# Power_Stage.net
KiCad netlist of a schematic drawn in Altium Designer
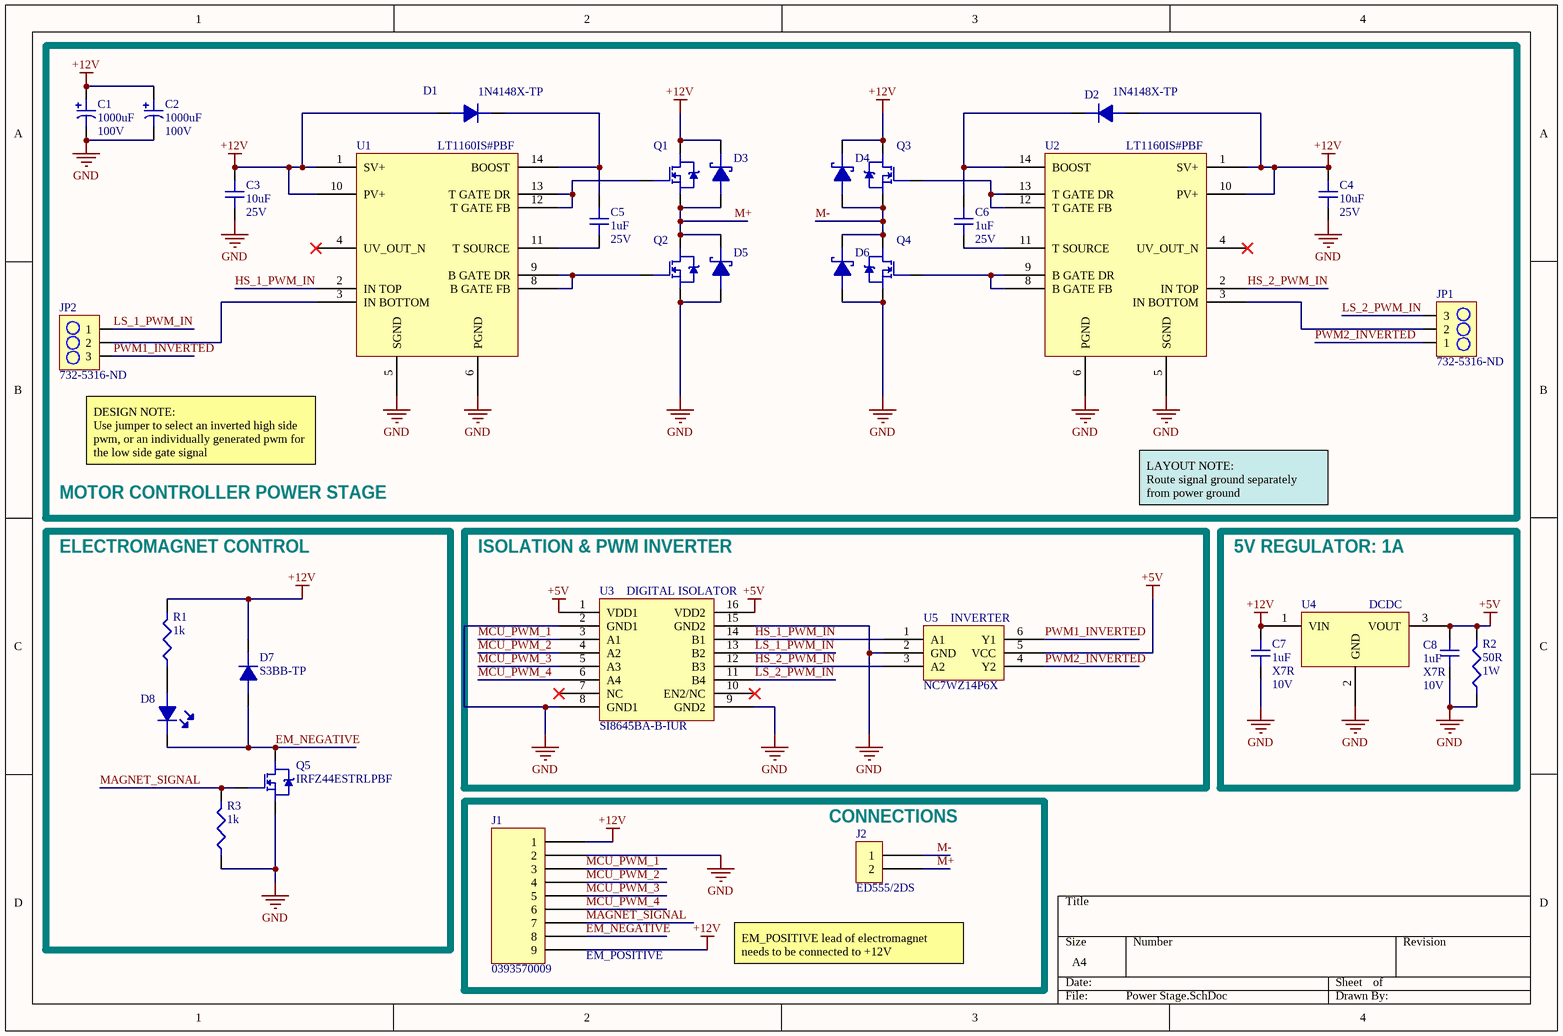
[diagram p0: Power Stage.SchDoc]

(export (version "E")
  (design (tool "Eeschema 10.0.6"))
  (components
    (comp (ref "C1")
      (value "UVR2A102MRD6")
      (footprint "CAP_THRU")
      (description "CAP Electrolytic 1000uF 100V")
      (fields
        (field (name "MANUFACTURER") "Nichicon")
        (field (name "TOLERANCE") "20%")
        (field (name "CAPACITANCE") "1000uF")
        (field (name "VOLTAGE RATING") "100V")
      )
      (libsource (lib "SCH_SYMBOLS") (part "UVR2A102MRD6"))
    )
    (comp (ref "C2")
      (value "UVR2A102MRD6")
      (footprint "CAP_THRU")
      (description "CAP Electrolytic 1000uF 100V")
      (fields
        (field (name "MANUFACTURER") "Nichicon")
        (field (name "TOLERANCE") "20%")
        (field (name "CAPACITANCE") "1000uF")
        (field (name "VOLTAGE RATING") "100V")
      )
      (libsource (lib "SCH_SYMBOLS") (part "UVR2A102MRD6"))
    )
    (comp (ref "C3")
      (value "C3216X5R1E106K160AB")
      (footprint "C1206")
      (fields
        (field (name "MANUFACTURER") "TDK")
        (field (name "TOLERANCE") "10%")
        (field (name "CAPACITANCE") "10uF")
        (field (name "VOLTAGE RATING") "25V")
      )
      (libsource (lib "SCH_SYMBOLS") (part "C3216X5R1E106K160AB"))
    )
    (comp (ref "C4")
      (value "C3216X5R1E106K160AB")
      (footprint "C1206")
      (fields
        (field (name "MANUFACTURER") "TDK")
        (field (name "TOLERANCE") "10%")
        (field (name "CAPACITANCE") "10uF")
        (field (name "VOLTAGE RATING") "25V")
      )
      (libsource (lib "SCH_SYMBOLS") (part "C3216X5R1E106K160AB"))
    )
    (comp (ref "C5")
      (value "1uF")
      (footprint "C0805")
      (description "CAP MLCC 1UF 25V X7R 0805")
      (fields
        (field (name "MANUFACTURER") "Murata")
        (field (name "MANUFACTURER PART NUMBER") "GCM21BR71E105KA56L")
        (field (name "CAPACITANCE") "1uF")
        (field (name "VOLTAGE") "25V")
      )
      (libsource (lib "SCH_SYMBOLS") (part "GCM21BR71E105KA56L"))
    )
    (comp (ref "C6")
      (value "1uF")
      (footprint "C0805")
      (description "CAP MLCC 1UF 25V X7R 0805")
      (fields
        (field (name "MANUFACTURER") "Murata")
        (field (name "MANUFACTURER PART NUMBER") "GCM21BR71E105KA56L")
        (field (name "CAPACITANCE") "1uF")
        (field (name "VOLTAGE") "25V")
      )
      (libsource (lib "SCH_SYMBOLS") (part "GCM21BR71E105KA56L"))
    )
    (comp (ref "C7")
      (value "1uF")
      (footprint "C0805")
      (description "CAP CER 1UF 10V X7R 0805")
      (fields
        (field (name "MANUFACTURER") "Kyocera AVX")
        (field (name "MANUFACTURER PART NUMBER") "0805ZC105KAT2A")
        (field (name "DIELECTRIC") "X7R")
        (field (name "VOLTAGE") "10V")
      )
      (libsource (lib "SCH_SYMBOLS") (part "0805ZC105KAT2A"))
    )
    (comp (ref "C8")
      (value "1uF")
      (footprint "C0805")
      (description "CAP CER 1UF 10V X7R 0805")
      (fields
        (field (name "MANUFACTURER") "Kyocera AVX")
        (field (name "MANUFACTURER PART NUMBER") "0805ZC105KAT2A")
        (field (name "DIELECTRIC") "X7R")
        (field (name "VOLTAGE") "10V")
      )
      (libsource (lib "SCH_SYMBOLS") (part "0805ZC105KAT2A"))
    )
    (comp (ref "D1")
      (value "1N4148X-TP")
      (footprint "SOD523")
      (description "DIODE GEN PURP 75V 150MA SOD523")
      (fields (field (name "MANUFACTURER") "MCC"))
      (libsource (lib "SCH_SYMBOLS") (part "1N4148X-TP"))
    )
    (comp (ref "D2")
      (value "1N4148X-TP")
      (footprint "SOD523")
      (description "DIODE GEN PURP 75V 150MA SOD523")
      (fields (field (name "MANUFACTURER") "MCC"))
      (libsource (lib "SCH_SYMBOLS") (part "1N4148X-TP"))
    )
    (comp (ref "D3")
      (value "CDBA540-HF")
      (footprint "DO214-AC")
      (description "DIODE Schottky Diodes & Rectifiers 40V, 5A")
      (fields (field (name "MANUFACTURER") "Comchip"))
      (libsource (lib "SCH_SYMBOLS") (part "CDBA540-HF"))
    )
    (comp (ref "D4")
      (value "CDBA540-HF")
      (footprint "DO214-AC")
      (description "DIODE Schottky Diodes & Rectifiers 40V, 5A")
      (fields (field (name "MANUFACTURER") "Comchip"))
      (libsource (lib "SCH_SYMBOLS") (part "CDBA540-HF"))
    )
    (comp (ref "D5")
      (value "CDBA540-HF")
      (footprint "DO214-AC")
      (description "DIODE Schottky Diodes & Rectifiers 40V, 5A")
      (fields (field (name "MANUFACTURER") "Comchip"))
      (libsource (lib "SCH_SYMBOLS") (part "CDBA540-HF"))
    )
    (comp (ref "D6")
      (value "CDBA540-HF")
      (footprint "DO214-AC")
      (description "DIODE Schottky Diodes & Rectifiers 40V, 5A")
      (fields (field (name "MANUFACTURER") "Comchip"))
      (libsource (lib "SCH_SYMBOLS") (part "CDBA540-HF"))
    )
    (comp (ref "D7")
      (value "S3BB-TP")
      (footprint "DO-214AA_Diode")
      (description "DIODE GEN PURP 100V 3A DO214AA")
      (fields (field (name "MANUFACTURER") "MCC"))
      (libsource (lib "SCH_SYMBOLS") (part "S3BB-TP"))
    )
    (comp (ref "D8")
      (value "LTST-C191TBKT-5A")
      (footprint "LED_0603")
      (description "LED BLUE CLEAR 0603 SMD")
      (fields (field (name "MANUFACTURER") "Vishay Lite-On") (field (name "VOLTAGE") "29V"))
      (libsource (lib "SCH_SYMBOLS") (part "LTST-C191TBKT-5A"))
    )
    (comp (ref "J1")
      (value "0393570009")
      (footprint "9POS_CONNECTOR")
      (description "CONN TERMINAL BLOCK 9POS 3.5MM")
      (fields (field (name "MANUFACTURER") "Molex") (field (name "VOLTAGE") "300V"))
      (libsource (lib "SCH_SYMBOLS") (part "0393570009"))
    )
    (comp (ref "J2")
      (value "ED555/2DS")
      (footprint "2POS_CONNECTOR")
      (description "TERMINAL BLOCK 3.5MM 2POS PCB")
      (fields (field (name "MANUFACTURER") "On-Shore Technology") (field (name "VOLTAGE") "150V"))
      (libsource (lib "SCH_SYMBOLS") (part "ED555/2DS"))
    )
    (comp (ref "JP1")
      (value "732-5316-ND")
      (footprint "3PIN_HEADER")
      (fields
        (field (name "MANUFACTURER") "Wurth Electronics")
        (field (name "MANUFACTURER PART NUMBER") "61300311121")
      )
      (libsource (lib "SCH_SYMBOLS") (part "61300311121"))
    )
    (comp (ref "JP2")
      (value "732-5316-ND")
      (footprint "3PIN_HEADER")
      (fields
        (field (name "MANUFACTURER") "Wurth Electronics")
        (field (name "MANUFACTURER PART NUMBER") "61300311121")
      )
      (libsource (lib "") (part "61300311121_1"))
    )
    (comp (ref "Q1")
      (value "IRFZ44ESTRLPBF")
      (footprint "D2PAK")
      (description "MOSFET N-CH 60V 48A D2PAK")
      (fields (field (name "MANUFACTURER") "Infineon"))
      (libsource (lib "SCH_SYMBOLS") (part "IRFZ44ESTRLPBF"))
    )
    (comp (ref "Q2")
      (value "IRFZ44ESTRLPBF")
      (footprint "D2PAK")
      (description "MOSFET N-CH 60V 48A D2PAK")
      (fields (field (name "MANUFACTURER") "Infineon"))
      (libsource (lib "SCH_SYMBOLS") (part "IRFZ44ESTRLPBF"))
    )
    (comp (ref "Q3")
      (value "IRFZ44ESTRLPBF")
      (footprint "D2PAK")
      (description "MOSFET N-CH 60V 48A D2PAK")
      (fields (field (name "MANUFACTURER") "Infineon"))
      (libsource (lib "SCH_SYMBOLS") (part "IRFZ44ESTRLPBF"))
    )
    (comp (ref "Q4")
      (value "IRFZ44ESTRLPBF")
      (footprint "D2PAK")
      (description "MOSFET N-CH 60V 48A D2PAK")
      (fields (field (name "MANUFACTURER") "Infineon"))
      (libsource (lib "SCH_SYMBOLS") (part "IRFZ44ESTRLPBF"))
    )
    (comp (ref "Q5")
      (value "IRFZ44ESTRLPBF")
      (footprint "D2PAK")
      (description "MOSFET N-CH 60V 48A D2PAK")
      (fields (field (name "MANUFACTURER") "Infineon"))
      (libsource (lib "SCH_SYMBOLS") (part "IRFZ44ESTRLPBF"))
    )
    (comp (ref "R1")
      (value "1k")
      (footprint "R0805")
      (description "RES SMD 1K OHM 0805 1K Ohm 0.1% 0.125W(1/8W) ±25ppm/C Molded SMD Automotive Punched T/R")
      (fields
        (field (name "MANUFACTURER") "Panasonic ECG")
        (field (name "MANUFACTURER PART NUMBER") "ERA-6AEB102V")
      )
      (libsource (lib "SCH_SYMBOLS") (part "ERA-6AEB102V"))
    )
    (comp (ref "R2")
      (value "50R")
      (footprint "R2512")
      (description "RES SMD 50 OHM 1% 1W 2515")
      (fields
        (field (name "MANUFACTURER") "Vishay Dale")
        (field (name "MANUFACTURER PART NUMBER") "WSC251550R00FEA")
        (field (name "POWER RATING") "1W")
      )
      (libsource (lib "SCH_SYMBOLS") (part "WSC251550R00FEA"))
    )
    (comp (ref "R3")
      (value "1k")
      (footprint "R0805")
      (description "RES SMD 1K OHM 0805 1K Ohm 0.1% 0.125W(1/8W) ±25ppm/C Molded SMD Automotive Punched T/R")
      (fields
        (field (name "MANUFACTURER") "Panasonic ECG")
        (field (name "MANUFACTURER PART NUMBER") "ERA-6AEB102V")
      )
      (libsource (lib "SCH_SYMBOLS") (part "ERA-6AEB102V"))
    )
    (comp (ref "U1")
      (value "LT1160IS#PBF")
      (footprint "SOIC-14")
      (description "IC PWR MOSFET DRIVER N-CH 14SOIC")
      (fields (field (name "MANUFACTURER") "Analog Devices / Linear Technology"))
      (libsource (lib "") (part "LT1160IS#PBF_1"))
    )
    (comp (ref "U2")
      (value "LT1160IS#PBF")
      (footprint "SOIC-14")
      (description "IC PWR MOSFET DRIVER N-CH 14SOIC")
      (fields (field (name "MANUFACTURER") "Analog Devices / Linear Technology"))
      (libsource (lib "SCH_SYMBOLS") (part "LT1160IS#PBF"))
    )
    (comp (ref "U3")
      (value "SI8645BA-B-IUR")
      (footprint "QSOP-16")
      (description "IC DIGITAL ISOLATOR 4CHANNEL 150MBPS 1000VRMS ISOLATION NO ISOLATED POWER")
      (fields (field (name "MANUFACTURER") "Silicon Labs"))
      (libsource (lib "SCH_SYMBOLS") (part "SI8645BA-B-IUR"))
    )
    (comp (ref "U4")
      (value "DCDC")
      (footprint "DCDC")
      (description "Non-Isolated DC/DC Converters 8-28Vin 5V 1.0A THRU")
      (fields (field (name "MANUFACTURER") "Recom") (field (name "MANUFACTURER PART NUMBER") "R-78E5.0-1.0"))
      (libsource (lib "SCH_SYMBOLS") (part "R-78E5.0-1.0"))
    )
    (comp (ref "U5")
      (value "NC7WZ14P6X")
      (footprint "TSOP-6")
      (description "IC INVERTER DUAL SCHMITT SC70-6")
      (fields (field (name "MANUFACTURER") "ON Semiconductor / Fairchild"))
      (libsource (lib "SCH_SYMBOLS") (part "NC7WZ14P6X"))
    )
  )
  (nets
    (net (code "1") (name "+5V") (class "Default")
      (node (ref "C8") (pin "2") (pinfunction "2_2") (pintype "passive"))
      (node (ref "R2") (pin "2") (pinfunction "2_2") (pintype "passive"))
      (node (ref "U3") (pin "1") (pinfunction "VDD1_1") (pintype "passive"))
      (node (ref "U3") (pin "16") (pinfunction "VDD2_16") (pintype "passive"))
      (node (ref "U4") (pin "3") (pinfunction "VOUT_3") (pintype "passive"))
      (node (ref "U5") (pin "5") (pinfunction "VCC_5") (pintype "passive"))
    )
    (net (code "2") (name "+12V") (class "Default")
      (node (ref "C1") (pin "1") (pinfunction "1_1") (pintype "passive"))
      (node (ref "C2") (pin "1") (pinfunction "1_1") (pintype "passive"))
      (node (ref "C3") (pin "2") (pinfunction "2_2") (pintype "passive"))
      (node (ref "C4") (pin "2") (pinfunction "2_2") (pintype "passive"))
      (node (ref "C7") (pin "2") (pinfunction "2_2") (pintype "passive"))
      (node (ref "D1") (pin "1") (pinfunction "1_1") (pintype "passive"))
      (node (ref "D2") (pin "1") (pinfunction "1_1") (pintype "passive"))
      (node (ref "D3") (pin "2") (pinfunction "2_2") (pintype "passive"))
      (node (ref "D4") (pin "2") (pinfunction "2_2") (pintype "passive"))
      (node (ref "D7") (pin "2") (pinfunction "2_2") (pintype "passive"))
      (node (ref "J1") (pin "1") (pinfunction "1_1") (pintype "passive"))
      (node (ref "J1") (pin "9") (pinfunction "9_9") (pintype "passive"))
      (node (ref "Q1") (pin "2") (pinfunction "2_2") (pintype "passive"))
      (node (ref "Q3") (pin "2") (pinfunction "2_2") (pintype "passive"))
      (node (ref "R1") (pin "2") (pinfunction "2_2") (pintype "passive"))
      (node (ref "U1") (pin "1") (pinfunction "SV+_1") (pintype "passive"))
      (node (ref "U1") (pin "10") (pinfunction "PV+_10") (pintype "passive"))
      (node (ref "U2") (pin "1") (pinfunction "SV+_1") (pintype "passive"))
      (node (ref "U2") (pin "10") (pinfunction "PV+_10") (pintype "passive"))
      (node (ref "U4") (pin "1") (pinfunction "VIN_1") (pintype "passive"))
    )
    (net (code "3") (name "/EM_NEGATIVE") (class "Default")
      (node (ref "D7") (pin "1") (pinfunction "1_1") (pintype "passive"))
      (node (ref "D8") (pin "2") (pinfunction "2_2") (pintype "passive"))
      (node (ref "J1") (pin "8") (pinfunction "8_8") (pintype "passive"))
      (node (ref "Q5") (pin "2") (pinfunction "2_2") (pintype "passive"))
    )
    (net (code "4") (name "/HS_1_PWM_IN") (class "Default")
      (node (ref "U1") (pin "2") (pinfunction "IN_TOP_2") (pintype "passive"))
      (node (ref "U3") (pin "14") (pinfunction "B1_14") (pintype "passive"))
      (node (ref "U5") (pin "1") (pinfunction "A1_1") (pintype "passive"))
    )
    (net (code "5") (name "/HS_2_PWM_IN") (class "Default")
      (node (ref "U2") (pin "2") (pinfunction "IN_TOP_2") (pintype "passive"))
      (node (ref "U3") (pin "12") (pinfunction "B3_12") (pintype "passive"))
      (node (ref "U5") (pin "3") (pinfunction "A2_3") (pintype "passive"))
    )
    (net (code "6") (name "/LS_1_PWM_IN") (class "Default")
      (node (ref "JP2") (pin "1") (pinfunction "1_1") (pintype "passive"))
      (node (ref "U3") (pin "13") (pinfunction "B2_13") (pintype "passive"))
    )
    (net (code "7") (name "/LS_2_PWM_IN") (class "Default")
      (node (ref "JP1") (pin "3") (pinfunction "3_3") (pintype "passive"))
      (node (ref "U3") (pin "11") (pinfunction "B4_11") (pintype "passive"))
    )
    (net (code "8") (name "/M+") (class "Default")
      (node (ref "D3") (pin "1") (pinfunction "1_1") (pintype "passive"))
      (node (ref "D5") (pin "2") (pinfunction "2_2") (pintype "passive"))
      (node (ref "J2") (pin "2") (pinfunction "2_2") (pintype "passive"))
      (node (ref "Q1") (pin "3") (pinfunction "3_3") (pintype "passive"))
      (node (ref "Q2") (pin "2") (pinfunction "2_2") (pintype "passive"))
    )
    (net (code "9") (name "/M-") (class "Default")
      (node (ref "D4") (pin "1") (pinfunction "1_1") (pintype "passive"))
      (node (ref "D6") (pin "2") (pinfunction "2_2") (pintype "passive"))
      (node (ref "J2") (pin "1") (pinfunction "1_1") (pintype "passive"))
      (node (ref "Q3") (pin "3") (pinfunction "3_3") (pintype "passive"))
      (node (ref "Q4") (pin "2") (pinfunction "2_2") (pintype "passive"))
    )
    (net (code "10") (name "/MAGNET_SIGNAL") (class "Default")
      (node (ref "J1") (pin "7") (pinfunction "7_7") (pintype "passive"))
      (node (ref "Q5") (pin "1") (pinfunction "1_1") (pintype "passive"))
      (node (ref "R3") (pin "2") (pinfunction "2_2") (pintype "passive"))
    )
    (net (code "11") (name "/MCU_PWM_1") (class "Default")
      (node (ref "J1") (pin "3") (pinfunction "3_3") (pintype "passive"))
      (node (ref "U3") (pin "3") (pinfunction "A1_3") (pintype "passive"))
    )
    (net (code "12") (name "/MCU_PWM_2") (class "Default")
      (node (ref "J1") (pin "4") (pinfunction "4_4") (pintype "passive"))
      (node (ref "U3") (pin "4") (pinfunction "A2_4") (pintype "passive"))
    )
    (net (code "13") (name "/MCU_PWM_3") (class "Default")
      (node (ref "J1") (pin "5") (pinfunction "5_5") (pintype "passive"))
      (node (ref "U3") (pin "5") (pinfunction "A3_5") (pintype "passive"))
    )
    (net (code "14") (name "/MCU_PWM_4") (class "Default")
      (node (ref "J1") (pin "6") (pinfunction "6_6") (pintype "passive"))
      (node (ref "U3") (pin "6") (pinfunction "A4_6") (pintype "passive"))
    )
    (net (code "15") (name "/PWM1_INVERTED") (class "Default")
      (node (ref "JP2") (pin "3") (pinfunction "3_3") (pintype "passive"))
      (node (ref "U5") (pin "6") (pinfunction "Y1_6") (pintype "passive"))
    )
    (net (code "16") (name "/PWM2_INVERTED") (class "Default")
      (node (ref "JP1") (pin "1") (pinfunction "1_1") (pintype "passive"))
      (node (ref "U5") (pin "4") (pinfunction "Y2_4") (pintype "passive"))
    )
    (net (code "17") (name "GND") (class "Default")
      (node (ref "C1") (pin "2") (pinfunction "2_2") (pintype "passive"))
      (node (ref "C2") (pin "2") (pinfunction "2_2") (pintype "passive"))
      (node (ref "C3") (pin "1") (pinfunction "1_1") (pintype "passive"))
      (node (ref "C4") (pin "1") (pinfunction "1_1") (pintype "passive"))
      (node (ref "C7") (pin "1") (pinfunction "1_1") (pintype "passive"))
      (node (ref "C8") (pin "1") (pinfunction "1_1") (pintype "passive"))
      (node (ref "D5") (pin "1") (pinfunction "1_1") (pintype "passive"))
      (node (ref "D6") (pin "1") (pinfunction "1_1") (pintype "passive"))
      (node (ref "J1") (pin "2") (pinfunction "2_2") (pintype "passive"))
      (node (ref "Q2") (pin "3") (pinfunction "3_3") (pintype "passive"))
      (node (ref "Q4") (pin "3") (pinfunction "3_3") (pintype "passive"))
      (node (ref "Q5") (pin "3") (pinfunction "3_3") (pintype "passive"))
      (node (ref "R2") (pin "1") (pinfunction "1_1") (pintype "passive"))
      (node (ref "R3") (pin "1") (pinfunction "1_1") (pintype "passive"))
      (node (ref "U1") (pin "5") (pinfunction "SGND_5") (pintype "passive"))
      (node (ref "U1") (pin "6") (pinfunction "PGND_6") (pintype "passive"))
      (node (ref "U2") (pin "5") (pinfunction "SGND_5") (pintype "passive"))
      (node (ref "U2") (pin "6") (pinfunction "PGND_6") (pintype "passive"))
      (node (ref "U3") (pin "15") (pinfunction "GND2_15") (pintype "passive"))
      (node (ref "U3") (pin "2") (pinfunction "GND1_2") (pintype "passive"))
      (node (ref "U3") (pin "8") (pinfunction "GND1_8") (pintype "passive"))
      (node (ref "U3") (pin "9") (pinfunction "GND2_9") (pintype "passive"))
      (node (ref "U4") (pin "2") (pinfunction "GND_2") (pintype "passive"))
      (node (ref "U5") (pin "2") (pinfunction "GND_2") (pintype "passive"))
    )
    (net (code "18") (name "Net-(D8-Pad1)") (class "Default")
      (node (ref "D8") (pin "1") (pinfunction "1_1") (pintype "passive"))
      (node (ref "R1") (pin "1") (pinfunction "1_1") (pintype "passive"))
    )
    (net (code "19") (name "Net-(U1-BOOST)") (class "Default")
      (node (ref "C5") (pin "2") (pinfunction "2_2") (pintype "passive"))
      (node (ref "D1") (pin "2") (pinfunction "2_2") (pintype "passive"))
      (node (ref "U1") (pin "14") (pinfunction "BOOST_14") (pintype "passive"))
    )
    (net (code "20") (name "Net-(U1-B_GATE_DR)") (class "Default")
      (node (ref "Q2") (pin "1") (pinfunction "1_1") (pintype "passive"))
      (node (ref "U1") (pin "8") (pinfunction "B_GATE_FB_8") (pintype "passive"))
      (node (ref "U1") (pin "9") (pinfunction "B_GATE_DR_9") (pintype "passive"))
    )
    (net (code "21") (name "Net-(U1-IN_BOTTOM)") (class "Default")
      (node (ref "JP2") (pin "2") (pinfunction "2_2") (pintype "passive"))
      (node (ref "U1") (pin "3") (pinfunction "IN_BOTTOM_3") (pintype "passive"))
    )
    (net (code "22") (name "Net-(U1-T_GATE_DR)") (class "Default")
      (node (ref "Q1") (pin "1") (pinfunction "1_1") (pintype "passive"))
      (node (ref "U1") (pin "12") (pinfunction "T_GATE_FB_12") (pintype "passive"))
      (node (ref "U1") (pin "13") (pinfunction "T_GATE_DR_13") (pintype "passive"))
    )
    (net (code "23") (name "Net-(U1-T_SOURCE)") (class "Default")
      (node (ref "C5") (pin "1") (pinfunction "1_1") (pintype "passive"))
      (node (ref "U1") (pin "11") (pinfunction "T_SOURCE_11") (pintype "passive"))
    )
    (net (code "24") (name "Net-(U2-BOOST)") (class "Default")
      (node (ref "C6") (pin "2") (pinfunction "2_2") (pintype "passive"))
      (node (ref "D2") (pin "2") (pinfunction "2_2") (pintype "passive"))
      (node (ref "U2") (pin "14") (pinfunction "BOOST_14") (pintype "passive"))
    )
    (net (code "25") (name "Net-(U2-B_GATE_DR)") (class "Default")
      (node (ref "Q4") (pin "1") (pinfunction "1_1") (pintype "passive"))
      (node (ref "U2") (pin "8") (pinfunction "B_GATE_FB_8") (pintype "passive"))
      (node (ref "U2") (pin "9") (pinfunction "B_GATE_DR_9") (pintype "passive"))
    )
    (net (code "26") (name "Net-(U2-IN_BOTTOM)") (class "Default")
      (node (ref "JP1") (pin "2") (pinfunction "2_2") (pintype "passive"))
      (node (ref "U2") (pin "3") (pinfunction "IN_BOTTOM_3") (pintype "passive"))
    )
    (net (code "27") (name "Net-(U2-T_GATE_DR)") (class "Default")
      (node (ref "Q3") (pin "1") (pinfunction "1_1") (pintype "passive"))
      (node (ref "U2") (pin "12") (pinfunction "T_GATE_FB_12") (pintype "passive"))
      (node (ref "U2") (pin "13") (pinfunction "T_GATE_DR_13") (pintype "passive"))
    )
    (net (code "28") (name "Net-(U2-T_SOURCE)") (class "Default")
      (node (ref "C6") (pin "1") (pinfunction "1_1") (pintype "passive"))
      (node (ref "U2") (pin "11") (pinfunction "T_SOURCE_11") (pintype "passive"))
    )
    (net (code "29") (name "unconnected-(U1-UV_OUT_N-Pad4)") (class "Default")
      (node (ref "U1") (pin "4") (pinfunction "UV_OUT_N_4") (pintype "passive+no_connect"))
    )
    (net (code "30") (name "unconnected-(U2-UV_OUT_N-Pad4)") (class "Default")
      (node (ref "U2") (pin "4") (pinfunction "UV_OUT_N_4") (pintype "passive+no_connect"))
    )
    (net (code "31") (name "unconnected-(U3-EN2{slash}NC-Pad10)") (class "Default")
      (node (ref "U3") (pin "10") (pinfunction "EN2/NC_10") (pintype "passive+no_connect"))
    )
    (net (code "32") (name "unconnected-(U3-NC-Pad7)") (class "Default")
      (node (ref "U3") (pin "7") (pinfunction "NC_7") (pintype "passive+no_connect"))
    )
  )
)
